# LPCB280_-_ANALOG.net
KiCad netlist of a schematic drawn in Altium Designer
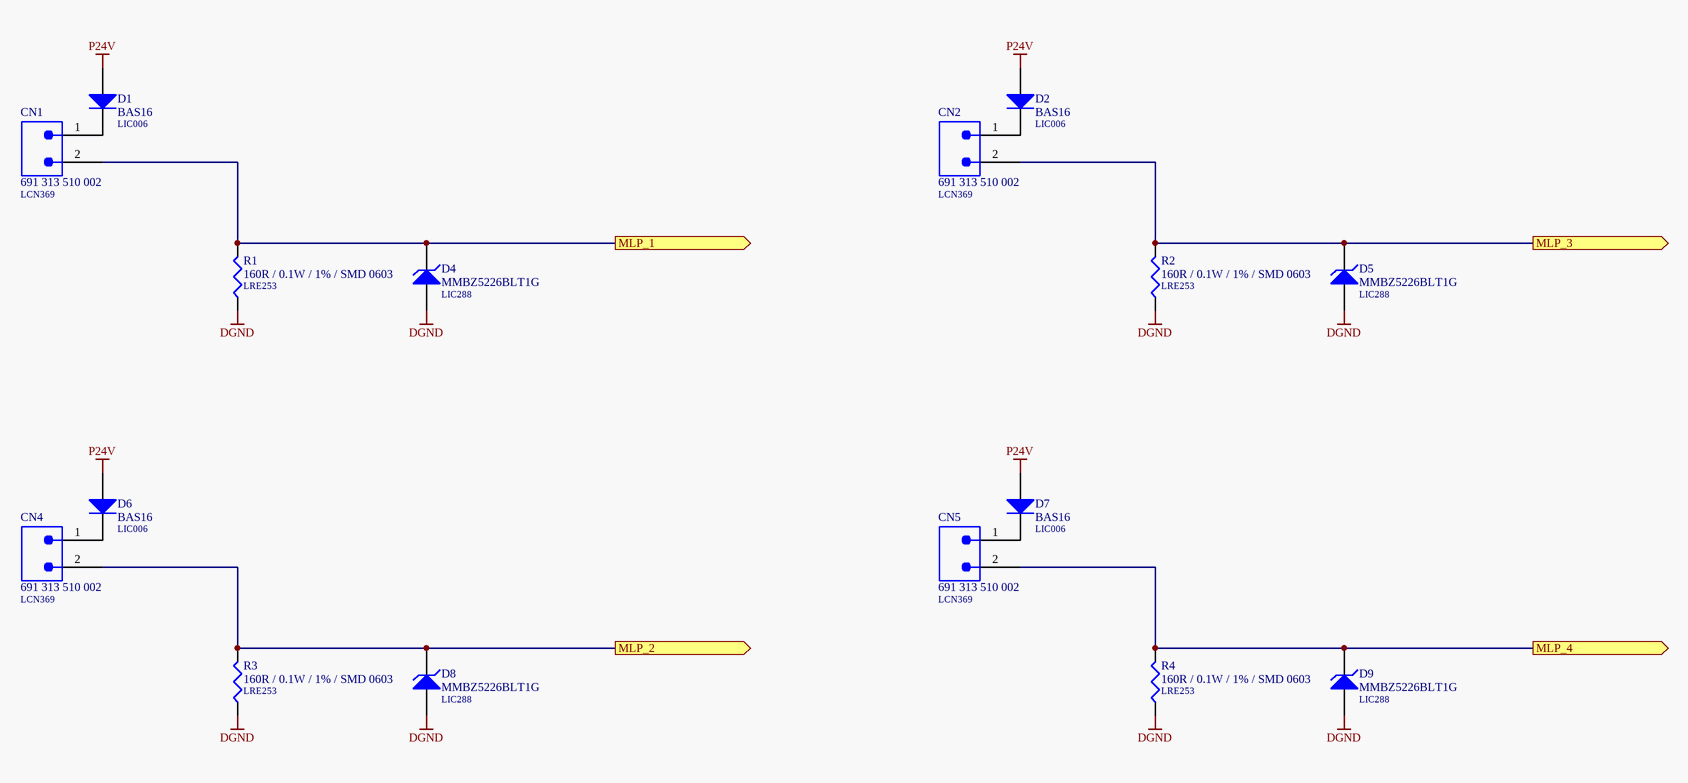
[diagram p0: LPCB280 - ANALOG.SchDoc]

(export (version "E")
  (design (tool "Eeschema 10.0.6"))
  (components
    (comp (ref "CN1")
      (value "691 313 510 002")
      (footprint "691 313 510 002")
      (description "Connector, Pluggable Terminal Block, 5.08mm, 2 Way, PTH")
      (fields (field (name "LDL_NUMBER") "LCN369"))
      (libsource (lib "LDL_Connectors") (part "691 313 510 002"))
    )
    (comp (ref "CN2")
      (value "691 313 510 002")
      (footprint "691 313 510 002")
      (description "Connector, Pluggable Terminal Block, 5.08mm, 2 Way, PTH")
      (fields (field (name "LDL_NUMBER") "LCN369"))
      (libsource (lib "LDL_Connectors") (part "691 313 510 002"))
    )
    (comp (ref "CN4")
      (value "691 313 510 002")
      (footprint "691 313 510 002")
      (description "Connector, Pluggable Terminal Block, 5.08mm, 2 Way, PTH")
      (fields (field (name "LDL_NUMBER") "LCN369"))
      (libsource (lib "LDL_Connectors") (part "691 313 510 002"))
    )
    (comp (ref "CN5")
      (value "691 313 510 002")
      (footprint "691 313 510 002")
      (description "Connector, Pluggable Terminal Block, 5.08mm, 2 Way, PTH")
      (fields (field (name "LDL_NUMBER") "LCN369"))
      (libsource (lib "LDL_Connectors") (part "691 313 510 002"))
    )
    (comp (ref "D1")
      (value "BAS16")
      (footprint "LFP021__SOT23")
      (description "Diode, Small Signal, 0.2A, 85V, SMD SOT-23 [LIC006]")
      (fields (field (name "LDL_NUMBER") "LIC006"))
      (libsource (lib "LDL_Semiconductors") (part "BAS16"))
    )
    (comp (ref "D2")
      (value "BAS16")
      (footprint "LFP021__SOT23")
      (description "Diode, Small Signal, 0.2A, 85V, SMD SOT-23 [LIC006]")
      (fields (field (name "LDL_NUMBER") "LIC006"))
      (libsource (lib "LDL_Semiconductors") (part "BAS16"))
    )
    (comp (ref "D4")
      (value "MMBZ5226BLT1G")
      (footprint "LFP021__SOT23")
      (description "Diode, Zener, 3.3V, 0.225W, SMD [LIC288]")
      (fields (field (name "LDL_NUMBER") "LIC288"))
      (libsource (lib "LDL_Semiconductors") (part "MMBZ5226BLT1G"))
    )
    (comp (ref "D5")
      (value "MMBZ5226BLT1G")
      (footprint "LFP021__SOT23")
      (description "Diode, Zener, 3.3V, 0.225W, SMD [LIC288]")
      (fields (field (name "LDL_NUMBER") "LIC288"))
      (libsource (lib "LDL_Semiconductors") (part "MMBZ5226BLT1G"))
    )
    (comp (ref "D6")
      (value "BAS16")
      (footprint "LFP021__SOT23")
      (description "Diode, Small Signal, 0.2A, 85V, SMD SOT-23 [LIC006]")
      (fields (field (name "LDL_NUMBER") "LIC006"))
      (libsource (lib "LDL_Semiconductors") (part "BAS16"))
    )
    (comp (ref "D7")
      (value "BAS16")
      (footprint "LFP021__SOT23")
      (description "Diode, Small Signal, 0.2A, 85V, SMD SOT-23 [LIC006]")
      (fields (field (name "LDL_NUMBER") "LIC006"))
      (libsource (lib "LDL_Semiconductors") (part "BAS16"))
    )
    (comp (ref "D8")
      (value "MMBZ5226BLT1G")
      (footprint "LFP021__SOT23")
      (description "Diode, Zener, 3.3V, 0.225W, SMD [LIC288]")
      (fields (field (name "LDL_NUMBER") "LIC288"))
      (libsource (lib "LDL_Semiconductors") (part "MMBZ5226BLT1G"))
    )
    (comp (ref "D9")
      (value "MMBZ5226BLT1G")
      (footprint "LFP021__SOT23")
      (description "Diode, Zener, 3.3V, 0.225W, SMD [LIC288]")
      (fields (field (name "LDL_NUMBER") "LIC288"))
      (libsource (lib "LDL_Semiconductors") (part "MMBZ5226BLT1G"))
    )
    (comp (ref "R1")
      (value "160R / 0.1W / 1% / SMD 0603")
      (footprint "LFP020__CR1608-0603-IPC7351_B")
      (description "Resistor, Ceramic Chip, 160R, 0.1W, 1%, SMD 0603 [LRE253]")
      (fields (field (name "LDL_NUMBER") "LRE253"))
      (libsource (lib "LDL_Resistors") (part "160R / 0.1W / 1% / SMD 0603"))
    )
    (comp (ref "R2")
      (value "160R / 0.1W / 1% / SMD 0603")
      (footprint "LFP020__CR1608-0603-IPC7351_B")
      (description "Resistor, Ceramic Chip, 160R, 0.1W, 1%, SMD 0603 [LRE253]")
      (fields (field (name "LDL_NUMBER") "LRE253"))
      (libsource (lib "LDL_Resistors") (part "160R / 0.1W / 1% / SMD 0603"))
    )
    (comp (ref "R3")
      (value "160R / 0.1W / 1% / SMD 0603")
      (footprint "LFP020__CR1608-0603-IPC7351_B")
      (description "Resistor, Ceramic Chip, 160R, 0.1W, 1%, SMD 0603 [LRE253]")
      (fields (field (name "LDL_NUMBER") "LRE253"))
      (libsource (lib "LDL_Resistors") (part "160R / 0.1W / 1% / SMD 0603"))
    )
    (comp (ref "R4")
      (value "160R / 0.1W / 1% / SMD 0603")
      (footprint "LFP020__CR1608-0603-IPC7351_B")
      (description "Resistor, Ceramic Chip, 160R, 0.1W, 1%, SMD 0603 [LRE253]")
      (fields (field (name "LDL_NUMBER") "LRE253"))
      (libsource (lib "LDL_Resistors") (part "160R / 0.1W / 1% / SMD 0603"))
    )
  )
  (nets
    (net (code "1") (name "/MLP_1") (class "Default")
      (node (ref "CN1") (pin "2") (pinfunction "2_2") (pintype "passive"))
      (node (ref "D4") (pin "3") (pinfunction "K_3") (pintype "passive"))
      (node (ref "R1") (pin "2") (pintype "passive"))
    )
    (net (code "2") (name "/MLP_2") (class "Default")
      (node (ref "CN4") (pin "2") (pinfunction "2_2") (pintype "passive"))
      (node (ref "D8") (pin "3") (pinfunction "K_3") (pintype "passive"))
      (node (ref "R3") (pin "2") (pintype "passive"))
    )
    (net (code "3") (name "/MLP_3") (class "Default")
      (node (ref "CN2") (pin "2") (pinfunction "2_2") (pintype "passive"))
      (node (ref "D5") (pin "3") (pinfunction "K_3") (pintype "passive"))
      (node (ref "R2") (pin "2") (pintype "passive"))
    )
    (net (code "4") (name "/MLP_4") (class "Default")
      (node (ref "CN5") (pin "2") (pinfunction "2_2") (pintype "passive"))
      (node (ref "D9") (pin "3") (pinfunction "K_3") (pintype "passive"))
      (node (ref "R4") (pin "2") (pintype "passive"))
    )
    (net (code "5") (name "DGND") (class "Default")
      (node (ref "D4") (pin "1") (pinfunction "A_1") (pintype "passive"))
      (node (ref "D5") (pin "1") (pinfunction "A_1") (pintype "passive"))
      (node (ref "D8") (pin "1") (pinfunction "A_1") (pintype "passive"))
      (node (ref "D9") (pin "1") (pinfunction "A_1") (pintype "passive"))
      (node (ref "R1") (pin "1") (pintype "passive"))
      (node (ref "R2") (pin "1") (pintype "passive"))
      (node (ref "R3") (pin "1") (pintype "passive"))
      (node (ref "R4") (pin "1") (pintype "passive"))
    )
    (net (code "6") (name "Net-(D1-K)") (class "Default")
      (node (ref "CN1") (pin "1") (pinfunction "1_1") (pintype "passive"))
      (node (ref "D1") (pin "3") (pinfunction "K_3") (pintype "passive"))
    )
    (net (code "7") (name "Net-(D2-K)") (class "Default")
      (node (ref "CN2") (pin "1") (pinfunction "1_1") (pintype "passive"))
      (node (ref "D2") (pin "3") (pinfunction "K_3") (pintype "passive"))
    )
    (net (code "8") (name "Net-(D6-K)") (class "Default")
      (node (ref "CN4") (pin "1") (pinfunction "1_1") (pintype "passive"))
      (node (ref "D6") (pin "3") (pinfunction "K_3") (pintype "passive"))
    )
    (net (code "9") (name "Net-(D7-K)") (class "Default")
      (node (ref "CN5") (pin "1") (pinfunction "1_1") (pintype "passive"))
      (node (ref "D7") (pin "3") (pinfunction "K_3") (pintype "passive"))
    )
    (net (code "10") (name "P24V") (class "Default")
      (node (ref "D1") (pin "1") (pinfunction "A_1") (pintype "passive"))
      (node (ref "D2") (pin "1") (pinfunction "A_1") (pintype "passive"))
      (node (ref "D6") (pin "1") (pinfunction "A_1") (pintype "passive"))
      (node (ref "D7") (pin "1") (pinfunction "A_1") (pintype "passive"))
    )
  )
)
